# ALLPRINT-CAPBOARD-677512-STEP-MOTOR-DRIV.net
KiCad netlist of a schematic drawn in Altium Designer
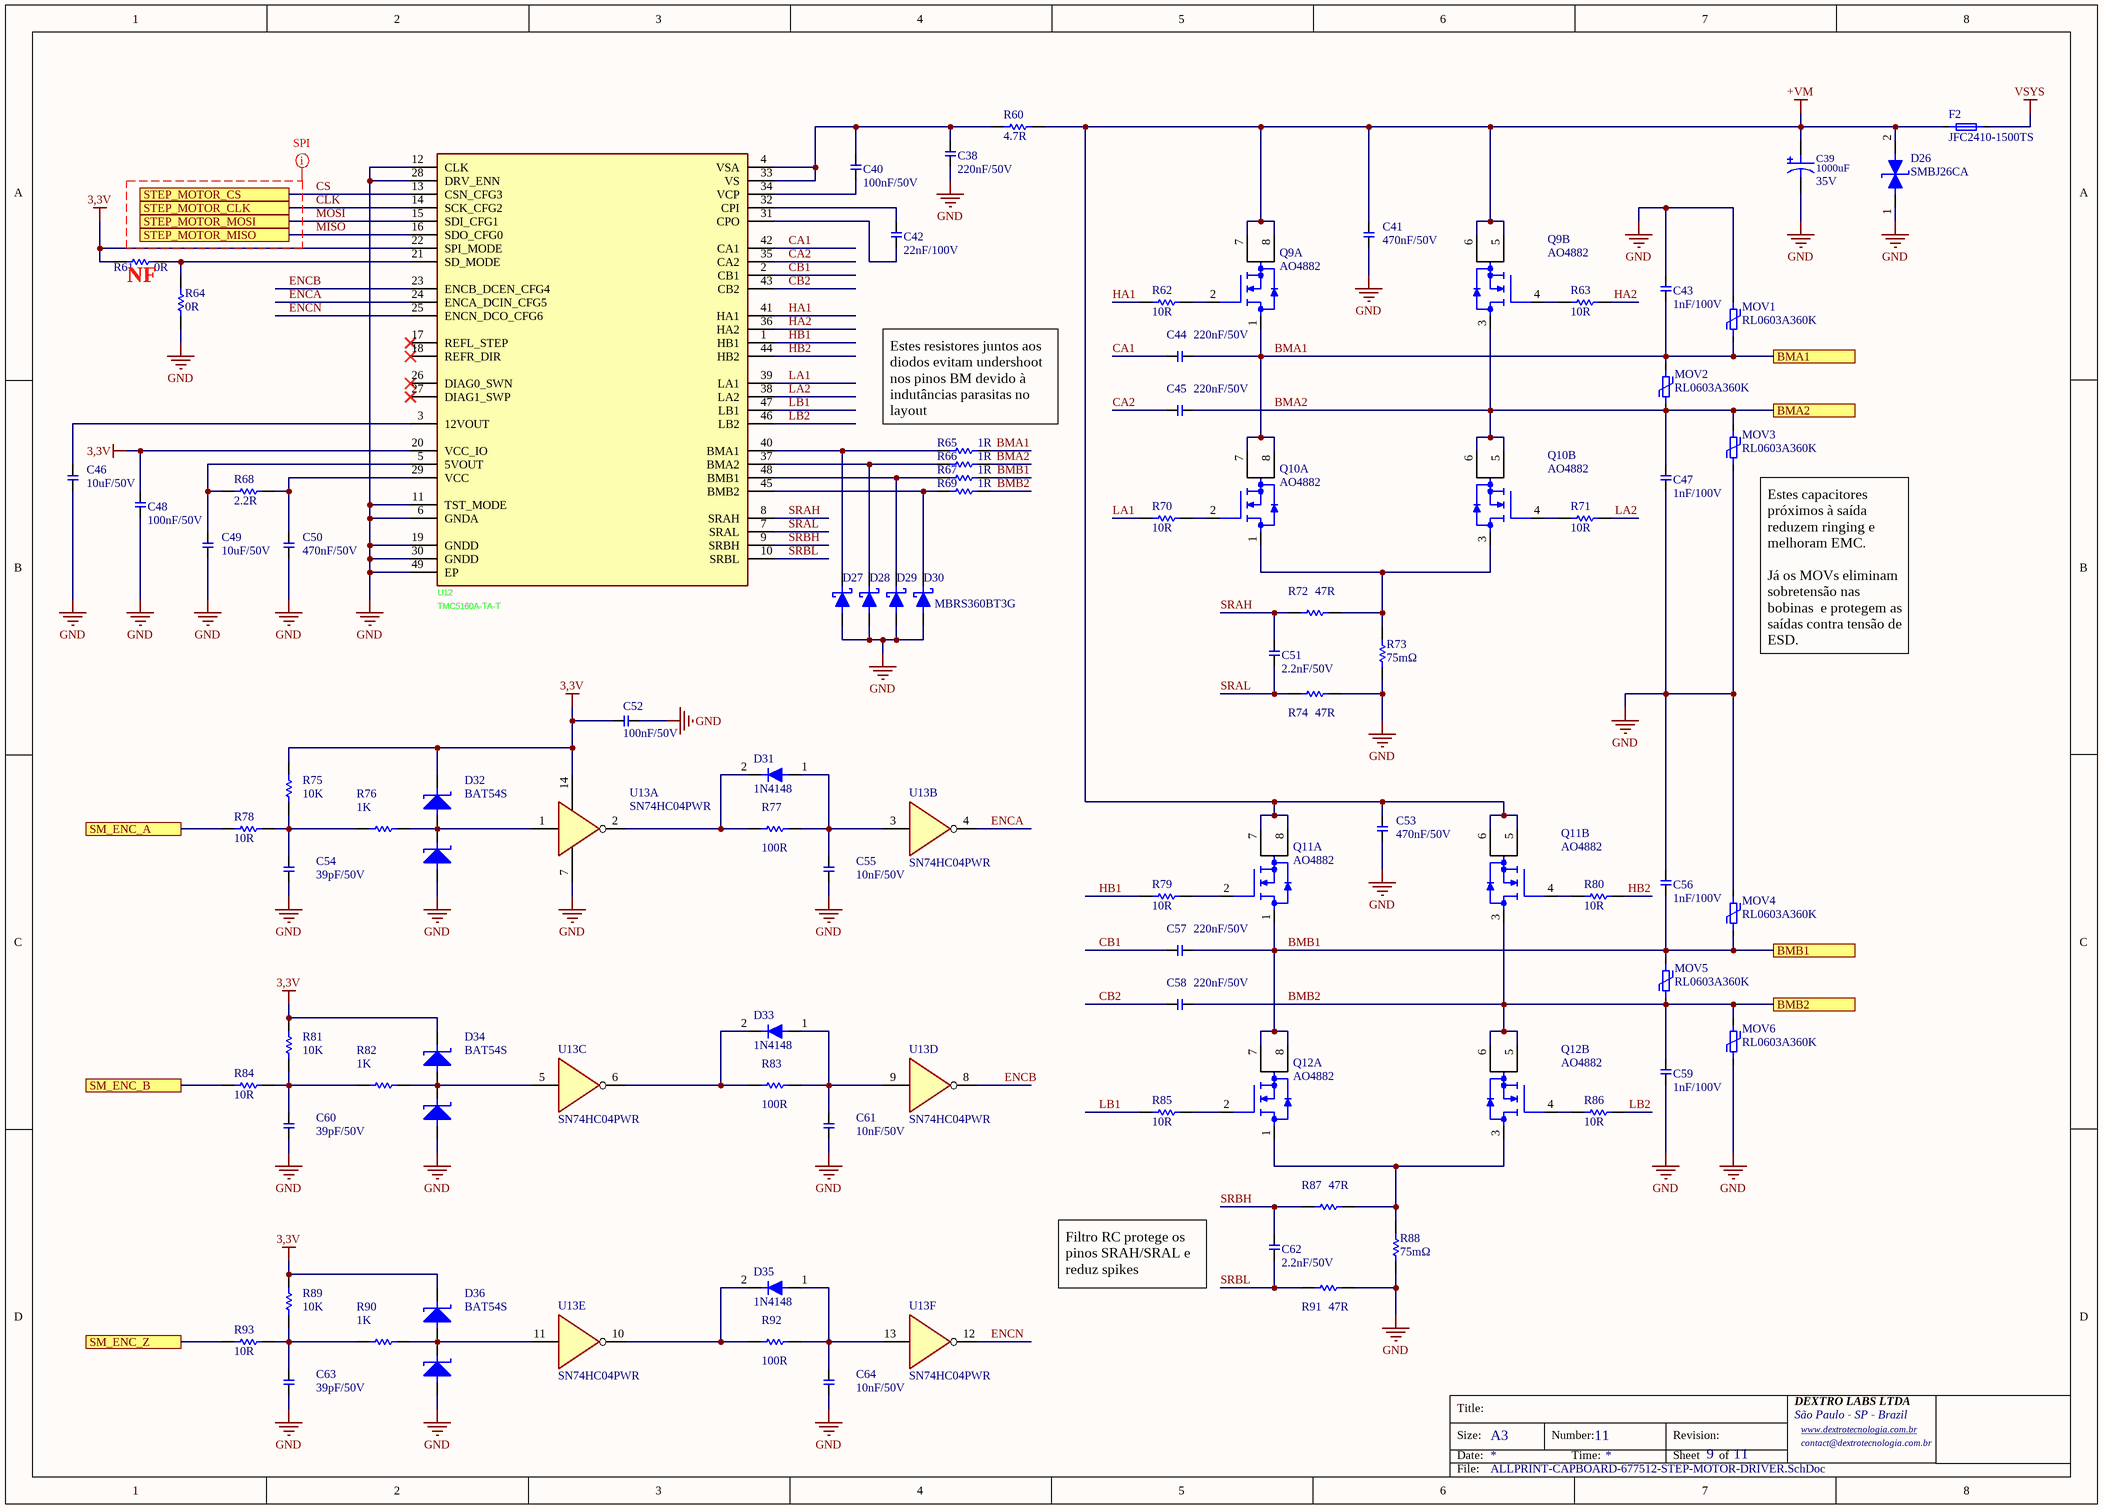
[diagram p0: ALLPRINT-CAPBOARD-677512-STEP-MOTOR-DRIVER.SchDoc]

(export (version "E")
  (design (tool "Eeschema 10.0.6"))
  (components
    (comp (ref "C38")
      (value "220nF/50V")
      (footprint "CAP-0603")
      (description "50V 220nF X7R ±10% 0603 Multilayer Ceramic Capacitors MLCC - SMD/SMT ROHS")
      (libsource (lib "dextro-labs") (part "CAP-220nF/50V-0603-X7R-MLCC"))
    )
    (comp (ref "C39")
      (value "1000uF")
      (footprint "CAP-ELET-D10-H20")
      (description "1000uF 35V ±20% Through Hole,D10xL20mm Aluminum Electrolytic Capacitors RoHS")
      (fields (field (name "VR") "35V"))
      (libsource (lib "dextro-labs") (part "CAP-1000uF-35V-D10-H20"))
    )
    (comp (ref "C40")
      (value "100nF/50V")
      (footprint "CAP-0603")
      (description "50V 100nF X7R ±10% 0603 Multilayer Ceramic Capacitors MLCC - SMD/SMT ROHS")
      (libsource (lib "dextro-labs") (part "CAP-100nF/50V-0603-X7R-MLCC"))
    )
    (comp (ref "C41")
      (value "470nF/50V")
      (footprint "CAP-0603")
      (description "50V 470nF X7R ±10% 0603 Multilayer Ceramic Capacitors MLCC - SMD/SMT ROHS")
      (libsource (lib "dextro-labs") (part "CAP-470nF/50V-0603-X7R-MLCC"))
    )
    (comp (ref "C42")
      (value "22nF/100V")
      (footprint "CAP-0805")
      (description "100V 22nF X7R ±10% 0805 Ceramic Capacitors RoHS")
      (libsource (lib "dextro-labs") (part "CAP-22nF/100V-0805-X7R-MLCC"))
    )
    (comp (ref "C43")
      (value "1nF/100V")
      (footprint "CAP-0805")
      (description "100V 1nF NP0 ±5% 0805 Ceramic Capacitors RoHS")
      (libsource (lib "dextro-labs") (part "CAP-1nF/100V-0805-NP0-MLCC"))
    )
    (comp (ref "C44")
      (value "220nF/50V")
      (footprint "CAP-0603")
      (description "50V 220nF X7R ±10% 0603 Multilayer Ceramic Capacitors MLCC - SMD/SMT ROHS")
      (libsource (lib "dextro-labs") (part "CAP-220nF/50V-0603-X7R-MLCC"))
    )
    (comp (ref "C45")
      (value "220nF/50V")
      (footprint "CAP-0603")
      (description "50V 220nF X7R ±10% 0603 Multilayer Ceramic Capacitors MLCC - SMD/SMT ROHS")
      (libsource (lib "dextro-labs") (part "CAP-220nF/50V-0603-X7R-MLCC"))
    )
    (comp (ref "C46")
      (value "10uF/50V")
      (footprint "CAP-0805")
      (description "50V 10uF X5R ±10% 1206 Multilayer Ceramic Capacitors MLCC - SMD/SMT ROHS")
      (libsource (lib "dextro-labs") (part "CAP-10uF/50V-0805-X5R-MLCC"))
    )
    (comp (ref "C47")
      (value "1nF/100V")
      (footprint "CAP-0805")
      (description "100V 1nF NP0 ±5% 0805 Ceramic Capacitors RoHS")
      (libsource (lib "dextro-labs") (part "CAP-1nF/100V-0805-NP0-MLCC"))
    )
    (comp (ref "C48")
      (value "100nF/50V")
      (footprint "CAP-0603")
      (description "50V 100nF X7R ±10% 0603 Multilayer Ceramic Capacitors MLCC - SMD/SMT ROHS")
      (libsource (lib "dextro-labs") (part "CAP-100nF/50V-0603-X7R-MLCC"))
    )
    (comp (ref "C49")
      (value "10uF/50V")
      (footprint "CAP-0805")
      (description "50V 10uF X5R ±10% 1206 Multilayer Ceramic Capacitors MLCC - SMD/SMT ROHS")
      (libsource (lib "dextro-labs") (part "CAP-10uF/50V-0805-X5R-MLCC"))
    )
    (comp (ref "C50")
      (value "470nF/50V")
      (footprint "CAP-0603")
      (description "50V 470nF X7R ±10% 0603 Multilayer Ceramic Capacitors MLCC - SMD/SMT ROHS")
      (libsource (lib "dextro-labs") (part "CAP-470nF/50V-0603-X7R-MLCC"))
    )
    (comp (ref "C51")
      (value "2.2nF/50V")
      (footprint "CAP-0603")
      (description "50V 2.2nF X7R ±10% 0603 Ceramic Capacitors RoHS")
      (libsource (lib "dextro-labs") (part "CAP-2.2nF/50V-0603-X7R-MLCC"))
    )
    (comp (ref "C52")
      (value "100nF/50V")
      (footprint "CAP-0603")
      (description "50V 100nF X7R ±10% 0603 Multilayer Ceramic Capacitors MLCC - SMD/SMT ROHS")
      (libsource (lib "dextro-labs") (part "CAP-100nF/50V-0603-X7R-MLCC"))
    )
    (comp (ref "C53")
      (value "470nF/50V")
      (footprint "CAP-0603")
      (description "50V 470nF X7R ±10% 0603 Multilayer Ceramic Capacitors MLCC - SMD/SMT ROHS")
      (libsource (lib "dextro-labs") (part "CAP-470nF/50V-0603-X7R-MLCC"))
    )
    (comp (ref "C54")
      (value "39pF/50V")
      (footprint "CAP-0603")
      (description "50V 39pF X7R ±10% 0603 Multilayer Ceramic Capacitors MLCC - SMD/SMT ROHS")
      (libsource (lib "dextro-labs") (part "CAP-39pF/50V-0603-X7R-MLCC"))
    )
    (comp (ref "C55")
      (value "10nF/50V")
      (footprint "CAP-0603")
      (description "50V 10nF X7R ±10% 0603 Multilayer Ceramic Capacitors MLCC - SMD/SMT ROHS")
      (libsource (lib "dextro-labs") (part "CAP-10nF/50V-0603-X7R-MLCC"))
    )
    (comp (ref "C56")
      (value "1nF/100V")
      (footprint "CAP-0805")
      (description "100V 1nF NP0 ±5% 0805 Ceramic Capacitors RoHS")
      (libsource (lib "dextro-labs") (part "CAP-1nF/100V-0805-NP0-MLCC"))
    )
    (comp (ref "C57")
      (value "220nF/50V")
      (footprint "CAP-0603")
      (description "50V 220nF X7R ±10% 0603 Multilayer Ceramic Capacitors MLCC - SMD/SMT ROHS")
      (libsource (lib "dextro-labs") (part "CAP-220nF/50V-0603-X7R-MLCC"))
    )
    (comp (ref "C58")
      (value "220nF/50V")
      (footprint "CAP-0603")
      (description "50V 220nF X7R ±10% 0603 Multilayer Ceramic Capacitors MLCC - SMD/SMT ROHS")
      (libsource (lib "dextro-labs") (part "CAP-220nF/50V-0603-X7R-MLCC"))
    )
    (comp (ref "C59")
      (value "1nF/100V")
      (footprint "CAP-0805")
      (description "100V 1nF NP0 ±5% 0805 Ceramic Capacitors RoHS")
      (libsource (lib "dextro-labs") (part "CAP-1nF/100V-0805-NP0-MLCC"))
    )
    (comp (ref "C60")
      (value "39pF/50V")
      (footprint "CAP-0603")
      (description "50V 39pF X7R ±10% 0603 Multilayer Ceramic Capacitors MLCC - SMD/SMT ROHS")
      (libsource (lib "dextro-labs") (part "CAP-39pF/50V-0603-X7R-MLCC"))
    )
    (comp (ref "C61")
      (value "10nF/50V")
      (footprint "CAP-0603")
      (description "50V 10nF X7R ±10% 0603 Multilayer Ceramic Capacitors MLCC - SMD/SMT ROHS")
      (libsource (lib "dextro-labs") (part "CAP-10nF/50V-0603-X7R-MLCC"))
    )
    (comp (ref "C62")
      (value "2.2nF/50V")
      (footprint "CAP-0603")
      (description "50V 2.2nF X7R ±10% 0603 Ceramic Capacitors RoHS")
      (libsource (lib "dextro-labs") (part "CAP-2.2nF/50V-0603-X7R-MLCC"))
    )
    (comp (ref "C63")
      (value "39pF/50V")
      (footprint "CAP-0603")
      (description "50V 39pF X7R ±10% 0603 Multilayer Ceramic Capacitors MLCC - SMD/SMT ROHS")
      (libsource (lib "dextro-labs") (part "CAP-39pF/50V-0603-X7R-MLCC"))
    )
    (comp (ref "C64")
      (value "10nF/50V")
      (footprint "CAP-0603")
      (description "50V 10nF X7R ±10% 0603 Multilayer Ceramic Capacitors MLCC - SMD/SMT ROHS")
      (libsource (lib "dextro-labs") (part "CAP-10nF/50V-0603-X7R-MLCC"))
    )
    (comp (ref "D26")
      (value "SMBJ26CA")
      (footprint "DO214-AA")
      (description "28.9V 26V 42.1V 14.2A 600W Bidirectional DO-214AA(SMB) TVS Diodes RoHS")
      (libsource (lib "dextro-labs") (part "SMBJ26CA"))
    )
    (comp (ref "D27")
      (value "MBRS360BT3G")
      (footprint "SOD-123FL")
      (description "Independent 60V 700mV@1A 1A SOD-123FL Single Diodes RoHS")
      (libsource (lib "dextro-labs") (part "DIODE-SCHOTTKY-60V-1A-DSK16"))
    )
    (comp (ref "D28")
      (value "MBRS360BT3G")
      (footprint "SOD-123FL")
      (description "Independent 60V 700mV@1A 1A SOD-123FL Single Diodes RoHS")
      (libsource (lib "dextro-labs") (part "DIODE-SCHOTTKY-60V-1A-DSK16"))
    )
    (comp (ref "D29")
      (value "MBRS360BT3G")
      (footprint "SOD-123FL")
      (description "Independent 60V 700mV@1A 1A SOD-123FL Single Diodes RoHS")
      (libsource (lib "dextro-labs") (part "DIODE-SCHOTTKY-60V-1A-DSK16"))
    )
    (comp (ref "D30")
      (value "MBRS360BT3G")
      (footprint "SOD-123FL")
      (description "Independent 60V 700mV@1A 1A SOD-123FL Single Diodes RoHS")
      (libsource (lib "dextro-labs") (part "DIODE-SCHOTTKY-60V-1A-DSK16"))
    )
    (comp (ref "D31")
      (value "1N4148")
      (footprint "SOD123")
      (description "1A 4ns 75V Independent 1V@50mA 150mA SOD-123 Single Diodes RoHS")
      (libsource (lib "dextro-labs") (part "1N4148"))
    )
    (comp (ref "D32")
      (value "BAT54S")
      (footprint "SOT23-3")
      (description "30V Dual 200mA 800mV@100mA SOT-23 Schottky Barrier Diodes (SBD) ROHS")
      (libsource (lib "dextro-labs") (part "BAT54S"))
    )
    (comp (ref "D33")
      (value "1N4148")
      (footprint "SOD123")
      (description "1A 4ns 75V Independent 1V@50mA 150mA SOD-123 Single Diodes RoHS")
      (libsource (lib "dextro-labs") (part "1N4148"))
    )
    (comp (ref "D34")
      (value "BAT54S")
      (footprint "SOT23-3")
      (description "30V Dual 200mA 800mV@100mA SOT-23 Schottky Barrier Diodes (SBD) ROHS")
      (libsource (lib "dextro-labs") (part "BAT54S"))
    )
    (comp (ref "D35")
      (value "1N4148")
      (footprint "SOD123")
      (description "1A 4ns 75V Independent 1V@50mA 150mA SOD-123 Single Diodes RoHS")
      (libsource (lib "dextro-labs") (part "1N4148"))
    )
    (comp (ref "D36")
      (value "BAT54S")
      (footprint "SOT23-3")
      (description "30V Dual 200mA 800mV@100mA SOT-23 Schottky Barrier Diodes (SBD) ROHS")
      (libsource (lib "dextro-labs") (part "BAT54S"))
    )
    (comp (ref "F2")
      (value "JFC2410-1500TS")
      (footprint "FUSE-2410")
      (description "250V Surface Mount Fuse 5A 2410 Fuses RoHS")
      (libsource (lib "dextro-labs") (part "FUSE-250V-5A-2410"))
    )
    (comp (ref "MOV1")
      (value "RL0603A360K")
      (footprint "MOV-0603")
      (description "78V 28V 21V 33.6V~42V 0603 Varistors, MOVs RoHS")
      (libsource (lib "dextro-labs") (part "MOV-RL0603A360K-SMD"))
    )
    (comp (ref "MOV2")
      (value "RL0603A360K")
      (footprint "MOV-0603")
      (description "78V 28V 21V 33.6V~42V 0603 Varistors, MOVs RoHS")
      (libsource (lib "dextro-labs") (part "MOV-RL0603A360K-SMD"))
    )
    (comp (ref "MOV3")
      (value "RL0603A360K")
      (footprint "MOV-0603")
      (description "78V 28V 21V 33.6V~42V 0603 Varistors, MOVs RoHS")
      (libsource (lib "dextro-labs") (part "MOV-RL0603A360K-SMD"))
    )
    (comp (ref "MOV4")
      (value "RL0603A360K")
      (footprint "MOV-0603")
      (description "78V 28V 21V 33.6V~42V 0603 Varistors, MOVs RoHS")
      (libsource (lib "dextro-labs") (part "MOV-RL0603A360K-SMD"))
    )
    (comp (ref "MOV5")
      (value "RL0603A360K")
      (footprint "MOV-0603")
      (description "78V 28V 21V 33.6V~42V 0603 Varistors, MOVs RoHS")
      (libsource (lib "dextro-labs") (part "MOV-RL0603A360K-SMD"))
    )
    (comp (ref "MOV6")
      (value "RL0603A360K")
      (footprint "MOV-0603")
      (description "78V 28V 21V 33.6V~42V 0603 Varistors, MOVs RoHS")
      (libsource (lib "dextro-labs") (part "MOV-RL0603A360K-SMD"))
    )
    (comp (ref "Q9")
      (value "AO4882")
      (footprint "SOIC-08")
      (description "40V 40A 2.4V 2 N-Channel SOIC-8 Single FETs, MOSFETs RoHS")
      (libsource (lib "dextro-labs") (part "AO4882"))
    )
    (comp (ref "Q10")
      (value "AO4882")
      (footprint "SOIC-08")
      (description "40V 40A 2.4V 2 N-Channel SOIC-8 Single FETs, MOSFETs RoHS")
      (libsource (lib "dextro-labs") (part "AO4882"))
    )
    (comp (ref "Q11")
      (value "AO4882")
      (footprint "SOIC-08")
      (description "40V 40A 2.4V 2 N-Channel SOIC-8 Single FETs, MOSFETs RoHS")
      (libsource (lib "dextro-labs") (part "AO4882"))
    )
    (comp (ref "Q12")
      (value "AO4882")
      (footprint "SOIC-08")
      (description "40V 40A 2.4V 2 N-Channel SOIC-8 Single FETs, MOSFETs RoHS")
      (libsource (lib "dextro-labs") (part "AO4882"))
    )
    (comp (ref "R60")
      (value "4.7R")
      (footprint "RES-0805")
      (description "125mW 4.7Ω 150V ±200ppm/℃ Thick Film Resistor ±1% 0805 Chip Resistor - Surface Mount RoHS")
      (libsource (lib "dextro-labs") (part "RES-4.7R-1%-125mW-0805"))
    )
    (comp (ref "R61")
      (value "0R")
      (footprint "RES-0603")
      (description "100mW 0Ω 75V Thick Film Resistor ±5% 0603 Chip Resistor - Surface Mount RoHS")
      (libsource (lib "dextro-labs") (part "RES-0R-1%-100mW-0603"))
    )
    (comp (ref "R62")
      (value "10R")
      (footprint "RES-0603")
      (description "100mW Thick Film Resistor 75V ±1% ±400ppm/℃ 10Ω 0603 Chip Resistor - Surface Mount ROHS")
      (libsource (lib "dextro-labs") (part "RES-10R-1%-100mW-0603"))
    )
    (comp (ref "R63")
      (value "10R")
      (footprint "RES-0603")
      (description "100mW Thick Film Resistor 75V ±1% ±400ppm/℃ 10Ω 0603 Chip Resistor - Surface Mount ROHS")
      (libsource (lib "dextro-labs") (part "RES-10R-1%-100mW-0603"))
    )
    (comp (ref "R64")
      (value "0R")
      (footprint "RES-0603")
      (description "100mW 0Ω 75V Thick Film Resistor ±5% 0603 Chip Resistor - Surface Mount RoHS")
      (libsource (lib "dextro-labs") (part "RES-0R-1%-100mW-0603"))
    )
    (comp (ref "R65")
      (value "1R")
      (footprint "RES-0603")
      (description "1Ω 100mW 75V ±200ppm/℃ Thick Film Resistor ±5% 0603 Chip Resistor - Surface Mount RoHS")
      (libsource (lib "dextro-labs") (part "RES-1R-1%-100mW-0603"))
    )
    (comp (ref "R66")
      (value "1R")
      (footprint "RES-0603")
      (description "1Ω 100mW 75V ±200ppm/℃ Thick Film Resistor ±5% 0603 Chip Resistor - Surface Mount RoHS")
      (libsource (lib "dextro-labs") (part "RES-1R-1%-100mW-0603"))
    )
    (comp (ref "R67")
      (value "1R")
      (footprint "RES-0603")
      (description "1Ω 100mW 75V ±200ppm/℃ Thick Film Resistor ±5% 0603 Chip Resistor - Surface Mount RoHS")
      (libsource (lib "dextro-labs") (part "RES-1R-1%-100mW-0603"))
    )
    (comp (ref "R68")
      (value "2.2R")
      (footprint "RES-0603")
      (description "2.2Ω 100mW 75V ±200ppm/℃ Thick Film Resistor ±5% 0603 Chip Resistor - Surface Mount RoHS")
      (libsource (lib "dextro-labs") (part "RES-2.2R-1%-100mW-0603"))
    )
    (comp (ref "R69")
      (value "1R")
      (footprint "RES-0603")
      (description "1Ω 100mW 75V ±200ppm/℃ Thick Film Resistor ±5% 0603 Chip Resistor - Surface Mount RoHS")
      (libsource (lib "dextro-labs") (part "RES-1R-1%-100mW-0603"))
    )
    (comp (ref "R70")
      (value "10R")
      (footprint "RES-0603")
      (description "100mW Thick Film Resistor 75V ±1% ±400ppm/℃ 10Ω 0603 Chip Resistor - Surface Mount ROHS")
      (libsource (lib "dextro-labs") (part "RES-10R-1%-100mW-0603"))
    )
    (comp (ref "R71")
      (value "10R")
      (footprint "RES-0603")
      (description "100mW Thick Film Resistor 75V ±1% ±400ppm/℃ 10Ω 0603 Chip Resistor - Surface Mount ROHS")
      (libsource (lib "dextro-labs") (part "RES-10R-1%-100mW-0603"))
    )
    (comp (ref "R72")
      (value "47R")
      (footprint "RES-0603")
      (description "100mW Thick Film Resistor 75V ±100ppm/℃ ±1% 47Ω 0603 Chip Resistor - Surface Mount ROHS")
      (libsource (lib "dextro-labs") (part "RES-47R-1%-100mW-0603"))
    )
    (comp (ref "R73")
      (value "75mΩ")
      (footprint "RES-2512")
      (description "3W 75mΩ Current Sense Resistor ±50ppm/℃ ±1% 2512 Current Sense Resistors RoHS")
      (libsource (lib "dextro-labs") (part "RES-75mΩ-1%-3W-2512"))
    )
    (comp (ref "R74")
      (value "47R")
      (footprint "RES-0603")
      (description "100mW Thick Film Resistor 75V ±100ppm/℃ ±1% 47Ω 0603 Chip Resistor - Surface Mount ROHS")
      (libsource (lib "dextro-labs") (part "RES-47R-1%-100mW-0603"))
    )
    (comp (ref "R75")
      (value "10K")
      (footprint "RES-0805")
      (description "100mW Thick Film Resistor 75V ±100ppm/℃ ±1% 10K Chip Resistor - Surface Mount ROHS")
      (libsource (lib "dextro-labs") (part "RES-10K-1%-125mW-0805"))
    )
    (comp (ref "R76")
      (value "1K")
      (footprint "RES-0603")
      (description "100mW Thick Film Resistor 75V ±100ppm/℃ ±1% 1kΩ 0603 Chip Resistor - Surface Mount ROHS")
      (libsource (lib "dextro-labs") (part "RES-1K-1%-100mW-0603"))
    )
    (comp (ref "R77")
      (value "100R")
      (footprint "RES-0603")
      (description "100mW Thick Film Resistor 75V ±100ppm/℃ ±1% 100Ω 0603 Chip Resistor - Surface Mount ROHS")
      (libsource (lib "dextro-labs") (part "RES-100R-1%-100mW-0603"))
    )
    (comp (ref "R78")
      (value "10R")
      (footprint "RES-0603")
      (description "100mW Thick Film Resistor 75V ±1% ±400ppm/℃ 10Ω 0603 Chip Resistor - Surface Mount ROHS")
      (libsource (lib "dextro-labs") (part "RES-10R-1%-100mW-0603"))
    )
    (comp (ref "R79")
      (value "10R")
      (footprint "RES-0603")
      (description "100mW Thick Film Resistor 75V ±1% ±400ppm/℃ 10Ω 0603 Chip Resistor - Surface Mount ROHS")
      (libsource (lib "dextro-labs") (part "RES-10R-1%-100mW-0603"))
    )
    (comp (ref "R80")
      (value "10R")
      (footprint "RES-0603")
      (description "100mW Thick Film Resistor 75V ±1% ±400ppm/℃ 10Ω 0603 Chip Resistor - Surface Mount ROHS")
      (libsource (lib "dextro-labs") (part "RES-10R-1%-100mW-0603"))
    )
    (comp (ref "R81")
      (value "10K")
      (footprint "RES-0805")
      (description "100mW Thick Film Resistor 75V ±100ppm/℃ ±1% 10K Chip Resistor - Surface Mount ROHS")
      (libsource (lib "dextro-labs") (part "RES-10K-1%-125mW-0805"))
    )
    (comp (ref "R82")
      (value "1K")
      (footprint "RES-0603")
      (description "100mW Thick Film Resistor 75V ±100ppm/℃ ±1% 1kΩ 0603 Chip Resistor - Surface Mount ROHS")
      (libsource (lib "dextro-labs") (part "RES-1K-1%-100mW-0603"))
    )
    (comp (ref "R83")
      (value "100R")
      (footprint "RES-0603")
      (description "100mW Thick Film Resistor 75V ±100ppm/℃ ±1% 100Ω 0603 Chip Resistor - Surface Mount ROHS")
      (libsource (lib "dextro-labs") (part "RES-100R-1%-100mW-0603"))
    )
    (comp (ref "R84")
      (value "10R")
      (footprint "RES-0603")
      (description "100mW Thick Film Resistor 75V ±1% ±400ppm/℃ 10Ω 0603 Chip Resistor - Surface Mount ROHS")
      (libsource (lib "dextro-labs") (part "RES-10R-1%-100mW-0603"))
    )
    (comp (ref "R85")
      (value "10R")
      (footprint "RES-0603")
      (description "100mW Thick Film Resistor 75V ±1% ±400ppm/℃ 10Ω 0603 Chip Resistor - Surface Mount ROHS")
      (libsource (lib "dextro-labs") (part "RES-10R-1%-100mW-0603"))
    )
    (comp (ref "R86")
      (value "10R")
      (footprint "RES-0603")
      (description "100mW Thick Film Resistor 75V ±1% ±400ppm/℃ 10Ω 0603 Chip Resistor - Surface Mount ROHS")
      (libsource (lib "dextro-labs") (part "RES-10R-1%-100mW-0603"))
    )
    (comp (ref "R87")
      (value "47R")
      (footprint "RES-0603")
      (description "100mW Thick Film Resistor 75V ±100ppm/℃ ±1% 47Ω 0603 Chip Resistor - Surface Mount ROHS")
      (libsource (lib "dextro-labs") (part "RES-47R-1%-100mW-0603"))
    )
    (comp (ref "R88")
      (value "75mΩ")
      (footprint "RES-2512")
      (description "3W 75mΩ Current Sense Resistor ±50ppm/℃ ±1% 2512 Current Sense Resistors RoHS")
      (libsource (lib "dextro-labs") (part "RES-75mΩ-1%-3W-2512"))
    )
    (comp (ref "R89")
      (value "10K")
      (footprint "RES-0805")
      (description "100mW Thick Film Resistor 75V ±100ppm/℃ ±1% 10K Chip Resistor - Surface Mount ROHS")
      (libsource (lib "dextro-labs") (part "RES-10K-1%-125mW-0805"))
    )
    (comp (ref "R90")
      (value "1K")
      (footprint "RES-0603")
      (description "100mW Thick Film Resistor 75V ±100ppm/℃ ±1% 1kΩ 0603 Chip Resistor - Surface Mount ROHS")
      (libsource (lib "dextro-labs") (part "RES-1K-1%-100mW-0603"))
    )
    (comp (ref "R91")
      (value "47R")
      (footprint "RES-0603")
      (description "100mW Thick Film Resistor 75V ±100ppm/℃ ±1% 47Ω 0603 Chip Resistor - Surface Mount ROHS")
      (libsource (lib "dextro-labs") (part "RES-47R-1%-100mW-0603"))
    )
    (comp (ref "R92")
      (value "100R")
      (footprint "RES-0603")
      (description "100mW Thick Film Resistor 75V ±100ppm/℃ ±1% 100Ω 0603 Chip Resistor - Surface Mount ROHS")
      (libsource (lib "dextro-labs") (part "RES-100R-1%-100mW-0603"))
    )
    (comp (ref "R93")
      (value "10R")
      (footprint "RES-0603")
      (description "100mW Thick Film Resistor 75V ±1% ±400ppm/℃ 10Ω 0603 Chip Resistor - Surface Mount ROHS")
      (libsource (lib "dextro-labs") (part "RES-10R-1%-100mW-0603"))
    )
    (comp (ref "U12")
      (value "TMC5160A-TA-T")
      (footprint "TQFP-48_L7.0-W7.0-P0.50-LS9.0-BL-EP")
      (fields (field (name "MANUFACTURER") "TRINAMIC"))
      (libsource (lib "dextro-labs") (part "TMC5160A-TA-T"))
    )
    (comp (ref "U13")
      (value "SN74HC04PWR")
      (footprint "TSSOP-14")
      (description "2V~6V 16ns@6V,50pF 2uA 6 1 TSSOP-14 Gates and Inverters RoHS")
      (libsource (lib "dextro-labs") (part "SN74HC04PWR"))
    )
  )
  (nets
    (net (code "1") (name "+VM") (class "Default")
      (node (ref "C39") (pin "1") (pinfunction "1_1") (pintype "passive"))
      (node (ref "C41") (pin "2") (pinfunction "2_2") (pintype "passive"))
      (node (ref "C53") (pin "2") (pinfunction "2_2") (pintype "passive"))
      (node (ref "D26") (pin "2") (pinfunction "A2_2") (pintype "passive"))
      (node (ref "F2") (pin "1") (pinfunction "1_1") (pintype "passive"))
      (node (ref "Q11") (pin "5") (pinfunction "D_5") (pintype "passive"))
      (node (ref "Q11") (pin "6") (pinfunction "D_6") (pintype "passive"))
      (node (ref "Q11") (pin "7") (pinfunction "D_7") (pintype "passive"))
      (node (ref "Q11") (pin "8") (pinfunction "D_8") (pintype "passive"))
      (node (ref "Q9") (pin "5") (pinfunction "D_5") (pintype "passive"))
      (node (ref "Q9") (pin "6") (pinfunction "D_6") (pintype "passive"))
      (node (ref "Q9") (pin "7") (pinfunction "D_7") (pintype "passive"))
      (node (ref "Q9") (pin "8") (pinfunction "D_8") (pintype "passive"))
      (node (ref "R60") (pin "2") (pinfunction "2_2") (pintype "passive"))
    )
    (net (code "2") (name "/BMA1") (class "Default")
      (node (ref "C43") (pin "1") (pinfunction "1_1") (pintype "passive"))
      (node (ref "C44") (pin "2") (pinfunction "2_2") (pintype "passive"))
      (node (ref "MOV1") (pin "1") (pinfunction "1_1") (pintype "passive"))
      (node (ref "MOV2") (pin "2") (pinfunction "2_2") (pintype "passive"))
      (node (ref "Q10") (pin "7") (pinfunction "D_7") (pintype "passive"))
      (node (ref "Q10") (pin "8") (pinfunction "D_8") (pintype "passive"))
      (node (ref "Q9") (pin "1") (pinfunction "S_1") (pintype "passive"))
      (node (ref "R65") (pin "2") (pinfunction "2_2") (pintype "passive"))
    )
    (net (code "3") (name "/BMA2") (class "Default")
      (node (ref "C45") (pin "2") (pinfunction "2_2") (pintype "passive"))
      (node (ref "C47") (pin "2") (pinfunction "2_2") (pintype "passive"))
      (node (ref "MOV2") (pin "1") (pinfunction "1_1") (pintype "passive"))
      (node (ref "MOV3") (pin "2") (pinfunction "2_2") (pintype "passive"))
      (node (ref "Q10") (pin "5") (pinfunction "D_5") (pintype "passive"))
      (node (ref "Q10") (pin "6") (pinfunction "D_6") (pintype "passive"))
      (node (ref "Q9") (pin "3") (pinfunction "S_3") (pintype "passive"))
      (node (ref "R66") (pin "2") (pinfunction "2_2") (pintype "passive"))
    )
    (net (code "4") (name "/BMB1") (class "Default")
      (node (ref "C56") (pin "1") (pinfunction "1_1") (pintype "passive"))
      (node (ref "C57") (pin "2") (pinfunction "2_2") (pintype "passive"))
      (node (ref "MOV4") (pin "1") (pinfunction "1_1") (pintype "passive"))
      (node (ref "MOV5") (pin "2") (pinfunction "2_2") (pintype "passive"))
      (node (ref "Q11") (pin "1") (pinfunction "S_1") (pintype "passive"))
      (node (ref "Q12") (pin "7") (pinfunction "D_7") (pintype "passive"))
      (node (ref "Q12") (pin "8") (pinfunction "D_8") (pintype "passive"))
      (node (ref "R67") (pin "2") (pinfunction "2_2") (pintype "passive"))
    )
    (net (code "5") (name "/BMB2") (class "Default")
      (node (ref "C58") (pin "2") (pinfunction "2_2") (pintype "passive"))
      (node (ref "C59") (pin "2") (pinfunction "2_2") (pintype "passive"))
      (node (ref "MOV5") (pin "1") (pinfunction "1_1") (pintype "passive"))
      (node (ref "MOV6") (pin "2") (pinfunction "2_2") (pintype "passive"))
      (node (ref "Q11") (pin "3") (pinfunction "S_3") (pintype "passive"))
      (node (ref "Q12") (pin "5") (pinfunction "D_5") (pintype "passive"))
      (node (ref "Q12") (pin "6") (pinfunction "D_6") (pintype "passive"))
      (node (ref "R69") (pin "2") (pinfunction "2_2") (pintype "passive"))
    )
    (net (code "6") (name "/CA1") (class "Default")
      (node (ref "C44") (pin "1") (pinfunction "1_1") (pintype "passive"))
      (node (ref "U12") (pin "42") (pinfunction "CA1_42") (pintype "passive"))
    )
    (net (code "7") (name "/CA2") (class "Default")
      (node (ref "C45") (pin "1") (pinfunction "1_1") (pintype "passive"))
      (node (ref "U12") (pin "35") (pinfunction "CA2_35") (pintype "passive"))
    )
    (net (code "8") (name "/CB1") (class "Default")
      (node (ref "C57") (pin "1") (pinfunction "1_1") (pintype "passive"))
      (node (ref "U12") (pin "2") (pinfunction "CB1_2") (pintype "passive"))
    )
    (net (code "9") (name "/CB2") (class "Default")
      (node (ref "C58") (pin "1") (pinfunction "1_1") (pintype "passive"))
      (node (ref "U12") (pin "43") (pinfunction "CB2_43") (pintype "passive"))
    )
    (net (code "10") (name "/CLK") (class "Default")
      (node (ref "U12") (pin "14") (pinfunction "SCK_CFG2_14") (pintype "passive"))
    )
    (net (code "11") (name "/CS") (class "Default")
      (node (ref "U12") (pin "13") (pinfunction "CSN_CFG3_13") (pintype "passive"))
    )
    (net (code "12") (name "/ENCA") (class "Default")
      (node (ref "U12") (pin "24") (pinfunction "ENCA_DCIN_CFG5_24") (pintype "passive"))
      (node (ref "U13") (pin "4") (pinfunction "4Y_4") (pintype "passive"))
    )
    (net (code "13") (name "/ENCB") (class "Default")
      (node (ref "U12") (pin "23") (pinfunction "ENCB_DCEN_CFG4_23") (pintype "passive"))
      (node (ref "U13") (pin "8") (pinfunction "8_8") (pintype "passive"))
    )
    (net (code "14") (name "/ENCN") (class "Default")
      (node (ref "U12") (pin "25") (pinfunction "ENCN_DCO_CFG6_25") (pintype "passive"))
      (node (ref "U13") (pin "12") (pinfunction "12_12") (pintype "passive"))
    )
    (net (code "15") (name "/HA1") (class "Default")
      (node (ref "R62") (pin "1") (pinfunction "1_1") (pintype "passive"))
      (node (ref "U12") (pin "41") (pinfunction "HA1_41") (pintype "passive"))
    )
    (net (code "16") (name "/HA2") (class "Default")
      (node (ref "R63") (pin "2") (pinfunction "2_2") (pintype "passive"))
      (node (ref "U12") (pin "36") (pinfunction "HA2_36") (pintype "passive"))
    )
    (net (code "17") (name "/HB1") (class "Default")
      (node (ref "R79") (pin "1") (pinfunction "1_1") (pintype "passive"))
      (node (ref "U12") (pin "1") (pinfunction "HB1_1") (pintype "passive"))
    )
    (net (code "18") (name "/HB2") (class "Default")
      (node (ref "R80") (pin "2") (pinfunction "2_2") (pintype "passive"))
      (node (ref "U12") (pin "44") (pinfunction "HB2_44") (pintype "passive"))
    )
    (net (code "19") (name "/LA1") (class "Default")
      (node (ref "R70") (pin "1") (pinfunction "1_1") (pintype "passive"))
      (node (ref "U12") (pin "39") (pinfunction "LA1_39") (pintype "passive"))
    )
    (net (code "20") (name "/LA2") (class "Default")
      (node (ref "R71") (pin "2") (pinfunction "2_2") (pintype "passive"))
      (node (ref "U12") (pin "38") (pinfunction "LA2_38") (pintype "passive"))
    )
    (net (code "21") (name "/LB1") (class "Default")
      (node (ref "R85") (pin "1") (pinfunction "1_1") (pintype "passive"))
      (node (ref "U12") (pin "47") (pinfunction "LB1_47") (pintype "passive"))
    )
    (net (code "22") (name "/LB2") (class "Default")
      (node (ref "R86") (pin "2") (pinfunction "2_2") (pintype "passive"))
      (node (ref "U12") (pin "46") (pinfunction "LB2_46") (pintype "passive"))
    )
    (net (code "23") (name "/MISO") (class "Default")
      (node (ref "U12") (pin "16") (pinfunction "SDO_CFG0_16") (pintype "passive"))
    )
    (net (code "24") (name "/MOSI") (class "Default")
      (node (ref "U12") (pin "15") (pinfunction "SDI_CFG1_15") (pintype "passive"))
    )
    (net (code "25") (name "/SM_ENC_A") (class "Default")
      (node (ref "R78") (pin "1") (pinfunction "1_1") (pintype "passive"))
    )
    (net (code "26") (name "/SM_ENC_B") (class "Default")
      (node (ref "R84") (pin "1") (pinfunction "1_1") (pintype "passive"))
    )
    (net (code "27") (name "/SM_ENC_Z") (class "Default")
      (node (ref "R93") (pin "1") (pinfunction "1_1") (pintype "passive"))
    )
    (net (code "28") (name "/SRAH") (class "Default")
      (node (ref "C51") (pin "2") (pinfunction "2_2") (pintype "passive"))
      (node (ref "R72") (pin "1") (pinfunction "1_1") (pintype "passive"))
      (node (ref "U12") (pin "8") (pinfunction "SRAH_8") (pintype "passive"))
    )
    (net (code "29") (name "/SRAL") (class "Default")
      (node (ref "C51") (pin "1") (pinfunction "1_1") (pintype "passive"))
      (node (ref "R74") (pin "1") (pinfunction "1_1") (pintype "passive"))
      (node (ref "U12") (pin "7") (pinfunction "SRAL_7") (pintype "passive"))
    )
    (net (code "30") (name "/SRBH") (class "Default")
      (node (ref "C62") (pin "2") (pinfunction "2_2") (pintype "passive"))
      (node (ref "R87") (pin "1") (pinfunction "1_1") (pintype "passive"))
      (node (ref "U12") (pin "9") (pinfunction "SRBH_9") (pintype "passive"))
    )
    (net (code "31") (name "/SRBL") (class "Default")
      (node (ref "C62") (pin "1") (pinfunction "1_1") (pintype "passive"))
      (node (ref "R91") (pin "1") (pinfunction "1_1") (pintype "passive"))
      (node (ref "U12") (pin "10") (pinfunction "SRBL_10") (pintype "passive"))
    )
    (net (code "32") (name "3,3V") (class "Default")
      (node (ref "C48") (pin "2") (pinfunction "2_2") (pintype "passive"))
      (node (ref "C52") (pin "2") (pinfunction "2_2") (pintype "passive"))
      (node (ref "D32") (pin "2") (pinfunction "2_2") (pintype "passive"))
      (node (ref "D34") (pin "2") (pinfunction "2_2") (pintype "passive"))
      (node (ref "D36") (pin "2") (pinfunction "2_2") (pintype "passive"))
      (node (ref "R61") (pin "2") (pinfunction "2_2") (pintype "passive"))
      (node (ref "R75") (pin "2") (pinfunction "2_2") (pintype "passive"))
      (node (ref "R81") (pin "2") (pinfunction "2_2") (pintype "passive"))
      (node (ref "R89") (pin "2") (pinfunction "2_2") (pintype "passive"))
      (node (ref "U12") (pin "20") (pinfunction "VCC_IO_20") (pintype "passive"))
      (node (ref "U12") (pin "22") (pinfunction "SPI_MODE_22") (pintype "passive"))
      (node (ref "U13") (pin "14") (pinfunction "VCC_14") (pintype "passive"))
    )
    (net (code "33") (name "GND") (class "Default")
      (node (ref "C38") (pin "1") (pinfunction "1_1") (pintype "passive"))
      (node (ref "C39") (pin "2") (pinfunction "2_2") (pintype "passive"))
      (node (ref "C41") (pin "1") (pinfunction "1_1") (pintype "passive"))
      (node (ref "C43") (pin "2") (pinfunction "2_2") (pintype "passive"))
      (node (ref "C46") (pin "1") (pinfunction "1_1") (pintype "passive"))
      (node (ref "C47") (pin "1") (pinfunction "1_1") (pintype "passive"))
      (node (ref "C48") (pin "1") (pinfunction "1_1") (pintype "passive"))
      (node (ref "C49") (pin "1") (pinfunction "1_1") (pintype "passive"))
      (node (ref "C50") (pin "1") (pinfunction "1_1") (pintype "passive"))
      (node (ref "C52") (pin "1") (pinfunction "1_1") (pintype "passive"))
      (node (ref "C53") (pin "1") (pinfunction "1_1") (pintype "passive"))
      (node (ref "C54") (pin "1") (pinfunction "1_1") (pintype "passive"))
      (node (ref "C55") (pin "1") (pinfunction "1_1") (pintype "passive"))
      (node (ref "C56") (pin "2") (pinfunction "2_2") (pintype "passive"))
      (node (ref "C59") (pin "1") (pinfunction "1_1") (pintype "passive"))
      (node (ref "C60") (pin "1") (pinfunction "1_1") (pintype "passive"))
      (node (ref "C61") (pin "1") (pinfunction "1_1") (pintype "passive"))
      (node (ref "C63") (pin "1") (pinfunction "1_1") (pintype "passive"))
      (node (ref "C64") (pin "1") (pinfunction "1_1") (pintype "passive"))
      (node (ref "D26") (pin "1") (pinfunction "A1_1") (pintype "passive"))
      (node (ref "D27") (pin "1") (pinfunction "A_1") (pintype "passive"))
      (node (ref "D28") (pin "1") (pinfunction "A_1") (pintype "passive"))
      (node (ref "D29") (pin "1") (pinfunction "A_1") (pintype "passive"))
      (node (ref "D30") (pin "1") (pinfunction "A_1") (pintype "passive"))
      (node (ref "D32") (pin "1") (pinfunction "1_1") (pintype "passive"))
      (node (ref "D34") (pin "1") (pinfunction "1_1") (pintype "passive"))
      (node (ref "D36") (pin "1") (pinfunction "1_1") (pintype "passive"))
      (node (ref "MOV1") (pin "2") (pinfunction "2_2") (pintype "passive"))
      (node (ref "MOV3") (pin "1") (pinfunction "1_1") (pintype "passive"))
      (node (ref "MOV4") (pin "2") (pinfunction "2_2") (pintype "passive"))
      (node (ref "MOV6") (pin "1") (pinfunction "1_1") (pintype "passive"))
      (node (ref "R64") (pin "1") (pinfunction "1_1") (pintype "passive"))
      (node (ref "R73") (pin "1") (pinfunction "1_1") (pintype "passive"))
      (node (ref "R74") (pin "2") (pinfunction "2_2") (pintype "passive"))
      (node (ref "R88") (pin "1") (pinfunction "1_1") (pintype "passive"))
      (node (ref "R91") (pin "2") (pinfunction "2_2") (pintype "passive"))
      (node (ref "U12") (pin "11") (pinfunction "TST_MODE_11") (pintype "passive"))
      (node (ref "U12") (pin "12") (pinfunction "CLK_12") (pintype "passive"))
      (node (ref "U12") (pin "19") (pinfunction "GNDD_19") (pintype "passive"))
      (node (ref "U12") (pin "28") (pinfunction "DRV_ENN_28") (pintype "passive"))
      (node (ref "U12") (pin "30") (pinfunction "GNDD_30") (pintype "passive"))
      (node (ref "U12") (pin "49") (pinfunction "EP_49") (pintype "passive"))
      (node (ref "U12") (pin "6") (pinfunction "GNDA_6") (pintype "passive"))
      (node (ref "U13") (pin "7") (pinfunction "GND_7") (pintype "passive"))
    )
    (net (code "34") (name "Net-(C54-Pad2)") (class "Default")
      (node (ref "C54") (pin "2") (pinfunction "2_2") (pintype "passive"))
      (node (ref "R75") (pin "1") (pinfunction "1_1") (pintype "passive"))
      (node (ref "R76") (pin "1") (pinfunction "1_1") (pintype "passive"))
      (node (ref "R78") (pin "2") (pinfunction "2_2") (pintype "passive"))
    )
    (net (code "35") (name "Net-(C60-Pad2)") (class "Default")
      (node (ref "C60") (pin "2") (pinfunction "2_2") (pintype "passive"))
      (node (ref "R81") (pin "1") (pinfunction "1_1") (pintype "passive"))
      (node (ref "R82") (pin "1") (pinfunction "1_1") (pintype "passive"))
      (node (ref "R84") (pin "2") (pinfunction "2_2") (pintype "passive"))
    )
    (net (code "36") (name "Net-(C63-Pad2)") (class "Default")
      (node (ref "C63") (pin "2") (pinfunction "2_2") (pintype "passive"))
      (node (ref "R89") (pin "1") (pinfunction "1_1") (pintype "passive"))
      (node (ref "R90") (pin "1") (pinfunction "1_1") (pintype "passive"))
      (node (ref "R93") (pin "2") (pinfunction "2_2") (pintype "passive"))
    )
    (net (code "37") (name "Net-(D27-K)") (class "Default")
      (node (ref "D27") (pin "2") (pinfunction "K_2") (pintype "passive"))
      (node (ref "R65") (pin "1") (pinfunction "1_1") (pintype "passive"))
      (node (ref "U12") (pin "40") (pinfunction "BMA1_40") (pintype "passive"))
    )
    (net (code "38") (name "Net-(D28-K)") (class "Default")
      (node (ref "D28") (pin "2") (pinfunction "K_2") (pintype "passive"))
      (node (ref "R66") (pin "1") (pinfunction "1_1") (pintype "passive"))
      (node (ref "U12") (pin "37") (pinfunction "BMA2_37") (pintype "passive"))
    )
    (net (code "39") (name "Net-(D29-K)") (class "Default")
      (node (ref "D29") (pin "2") (pinfunction "K_2") (pintype "passive"))
      (node (ref "R67") (pin "1") (pinfunction "1_1") (pintype "passive"))
      (node (ref "U12") (pin "48") (pinfunction "BMB1_48") (pintype "passive"))
    )
    (net (code "40") (name "Net-(D30-K)") (class "Default")
      (node (ref "D30") (pin "2") (pinfunction "K_2") (pintype "passive"))
      (node (ref "R69") (pin "1") (pinfunction "1_1") (pintype "passive"))
      (node (ref "U12") (pin "45") (pinfunction "BMB2_45") (pintype "passive"))
    )
    (net (code "41") (name "Net-(D31-A1)") (class "Default")
      (node (ref "C55") (pin "2") (pinfunction "2_2") (pintype "passive"))
      (node (ref "D31") (pin "1") (pinfunction "A1_1") (pintype "passive"))
      (node (ref "R77") (pin "2") (pinfunction "2_2") (pintype "passive"))
      (node (ref "U13") (pin "3") (pinfunction "4A_3") (pintype "passive"))
    )
    (net (code "42") (name "Net-(D31-K)") (class "Default")
      (node (ref "D31") (pin "2") (pinfunction "K_2") (pintype "passive"))
      (node (ref "R77") (pin "1") (pinfunction "1_1") (pintype "passive"))
      (node (ref "U13") (pin "2") (pinfunction "2_2") (pintype "passive"))
    )
    (net (code "43") (name "Net-(D33-A1)") (class "Default")
      (node (ref "C61") (pin "2") (pinfunction "2_2") (pintype "passive"))
      (node (ref "D33") (pin "1") (pinfunction "A1_1") (pintype "passive"))
      (node (ref "R83") (pin "2") (pinfunction "2_2") (pintype "passive"))
      (node (ref "U13") (pin "9") (pinfunction "9_9") (pintype "passive"))
    )
    (net (code "44") (name "Net-(D33-K)") (class "Default")
      (node (ref "D33") (pin "2") (pinfunction "K_2") (pintype "passive"))
      (node (ref "R83") (pin "1") (pinfunction "1_1") (pintype "passive"))
      (node (ref "U13") (pin "6") (pinfunction "6_6") (pintype "passive"))
    )
    (net (code "45") (name "Net-(D34-Pad3)") (class "Default")
      (node (ref "D34") (pin "3") (pinfunction "3_3") (pintype "passive"))
      (node (ref "R82") (pin "2") (pinfunction "2_2") (pintype "passive"))
      (node (ref "U13") (pin "5") (pinfunction "5_5") (pintype "passive"))
    )
    (net (code "46") (name "Net-(D35-A1)") (class "Default")
      (node (ref "C64") (pin "2") (pinfunction "2_2") (pintype "passive"))
      (node (ref "D35") (pin "1") (pinfunction "A1_1") (pintype "passive"))
      (node (ref "R92") (pin "2") (pinfunction "2_2") (pintype "passive"))
      (node (ref "U13") (pin "13") (pinfunction "13_13") (pintype "passive"))
    )
    (net (code "47") (name "Net-(D35-K)") (class "Default")
      (node (ref "D35") (pin "2") (pinfunction "K_2") (pintype "passive"))
      (node (ref "R92") (pin "1") (pinfunction "1_1") (pintype "passive"))
      (node (ref "U13") (pin "10") (pinfunction "10_10") (pintype "passive"))
    )
    (net (code "48") (name "Net-(D36-Pad3)") (class "Default")
      (node (ref "D36") (pin "3") (pinfunction "3_3") (pintype "passive"))
      (node (ref "R90") (pin "2") (pinfunction "2_2") (pintype "passive"))
      (node (ref "U13") (pin "11") (pinfunction "11_11") (pintype "passive"))
    )
    (net (code "49") (name "Net-(Q9A-G)") (class "Default")
      (node (ref "Q9") (pin "2") (pinfunction "G_2") (pintype "passive"))
      (node (ref "R62") (pin "2") (pinfunction "2_2") (pintype "passive"))
    )
    (net (code "50") (name "Net-(Q9B-G)") (class "Default")
      (node (ref "Q9") (pin "4") (pinfunction "G_4") (pintype "passive"))
      (node (ref "R63") (pin "1") (pinfunction "1_1") (pintype "passive"))
    )
    (net (code "51") (name "Net-(Q10A-G)") (class "Default")
      (node (ref "Q10") (pin "2") (pinfunction "G_2") (pintype "passive"))
      (node (ref "R70") (pin "2") (pinfunction "2_2") (pintype "passive"))
    )
    (net (code "52") (name "Net-(Q10A-S)") (class "Default")
      (node (ref "Q10") (pin "1") (pinfunction "S_1") (pintype "passive"))
      (node (ref "Q10") (pin "3") (pinfunction "S_3") (pintype "passive"))
      (node (ref "R72") (pin "2") (pinfunction "2_2") (pintype "passive"))
      (node (ref "R73") (pin "2") (pinfunction "2_2") (pintype "passive"))
    )
    (net (code "53") (name "Net-(Q10B-G)") (class "Default")
      (node (ref "Q10") (pin "4") (pinfunction "G_4") (pintype "passive"))
      (node (ref "R71") (pin "1") (pinfunction "1_1") (pintype "passive"))
    )
    (net (code "54") (name "Net-(Q11A-G)") (class "Default")
      (node (ref "Q11") (pin "2") (pinfunction "G_2") (pintype "passive"))
      (node (ref "R79") (pin "2") (pinfunction "2_2") (pintype "passive"))
    )
    (net (code "55") (name "Net-(Q11B-G)") (class "Default")
      (node (ref "Q11") (pin "4") (pinfunction "G_4") (pintype "passive"))
      (node (ref "R80") (pin "1") (pinfunction "1_1") (pintype "passive"))
    )
    (net (code "56") (name "Net-(Q12A-G)") (class "Default")
      (node (ref "Q12") (pin "2") (pinfunction "G_2") (pintype "passive"))
      (node (ref "R85") (pin "2") (pinfunction "2_2") (pintype "passive"))
    )
    (net (code "57") (name "Net-(Q12A-S)") (class "Default")
      (node (ref "Q12") (pin "1") (pinfunction "S_1") (pintype "passive"))
      (node (ref "Q12") (pin "3") (pinfunction "S_3") (pintype "passive"))
      (node (ref "R87") (pin "2") (pinfunction "2_2") (pintype "passive"))
      (node (ref "R88") (pin "2") (pinfunction "2_2") (pintype "passive"))
    )
    (net (code "58") (name "Net-(Q12B-G)") (class "Default")
      (node (ref "Q12") (pin "4") (pinfunction "G_4") (pintype "passive"))
      (node (ref "R86") (pin "1") (pinfunction "1_1") (pintype "passive"))
    )
    (net (code "59") (name "Net-(U12-5VOUT)") (class "Default")
      (node (ref "C49") (pin "2") (pinfunction "2_2") (pintype "passive"))
      (node (ref "R68") (pin "1") (pinfunction "1_1") (pintype "passive"))
      (node (ref "U12") (pin "5") (pinfunction "5VOUT_5") (pintype "passive"))
    )
    (net (code "60") (name "Net-(U12-12VOUT)") (class "Default")
      (node (ref "C46") (pin "2") (pinfunction "2_2") (pintype "passive"))
      (node (ref "U12") (pin "3") (pinfunction "12VOUT_3") (pintype "passive"))
    )
    (net (code "61") (name "Net-(U12-CPI)") (class "Default")
      (node (ref "C42") (pin "2") (pinfunction "2_2") (pintype "passive"))
      (node (ref "U12") (pin "32") (pinfunction "CPI_32") (pintype "passive"))
    )
    (net (code "62") (name "Net-(U12-CPO)") (class "Default")
      (node (ref "C42") (pin "1") (pinfunction "1_1") (pintype "passive"))
      (node (ref "U12") (pin "31") (pinfunction "CPO_31") (pintype "passive"))
    )
    (net (code "63") (name "Net-(U12-SD_MODE)") (class "Default")
      (node (ref "R61") (pin "1") (pinfunction "1_1") (pintype "passive"))
      (node (ref "R64") (pin "2") (pinfunction "2_2") (pintype "passive"))
      (node (ref "U12") (pin "21") (pinfunction "SD_MODE_21") (pintype "passive"))
    )
    (net (code "64") (name "Net-(U12-VCC)") (class "Default")
      (node (ref "C50") (pin "2") (pinfunction "2_2") (pintype "passive"))
      (node (ref "R68") (pin "2") (pinfunction "2_2") (pintype "passive"))
      (node (ref "U12") (pin "29") (pinfunction "VCC_29") (pintype "passive"))
    )
    (net (code "65") (name "Net-(U12-VCP)") (class "Default")
      (node (ref "C40") (pin "1") (pinfunction "1_1") (pintype "passive"))
      (node (ref "U12") (pin "34") (pinfunction "VCP_34") (pintype "passive"))
    )
    (net (code "66") (name "Net-(U12-VS)") (class "Default")
      (node (ref "C38") (pin "2") (pinfunction "2_2") (pintype "passive"))
      (node (ref "C40") (pin "2") (pinfunction "2_2") (pintype "passive"))
      (node (ref "R60") (pin "1") (pinfunction "1_1") (pintype "passive"))
      (node (ref "U12") (pin "33") (pinfunction "VS_33") (pintype "passive"))
      (node (ref "U12") (pin "4") (pinfunction "VSA_4") (pintype "passive"))
    )
    (net (code "67") (name "Net-(U13A-1A)") (class "Default")
      (node (ref "D32") (pin "3") (pinfunction "3_3") (pintype "passive"))
      (node (ref "R76") (pin "2") (pinfunction "2_2") (pintype "passive"))
      (node (ref "U13") (pin "1") (pinfunction "1A_1") (pintype "passive"))
    )
    (net (code "68") (name "VSYS") (class "Default")
      (node (ref "F2") (pin "2") (pinfunction "2_2") (pintype "passive"))
    )
    (net (code "69") (name "unconnected-(U12-DIAG0_SWN-Pad26)") (class "Default")
      (node (ref "U12") (pin "26") (pinfunction "DIAG0_SWN_26") (pintype "passive+no_connect"))
    )
    (net (code "70") (name "unconnected-(U12-DIAG1_SWP-Pad27)") (class "Default")
      (node (ref "U12") (pin "27") (pinfunction "DIAG1_SWP_27") (pintype "passive+no_connect"))
    )
    (net (code "71") (name "unconnected-(U12-REFL_STEP-Pad17)") (class "Default")
      (node (ref "U12") (pin "17") (pinfunction "REFL_STEP_17") (pintype "passive+no_connect"))
    )
    (net (code "72") (name "unconnected-(U12-REFR_DIR-Pad18)") (class "Default")
      (node (ref "U12") (pin "18") (pinfunction "REFR_DIR_18") (pintype "passive+no_connect"))
    )
  )
)
